# 1593K-WirelessTallyReceiver.net
KiCad netlist of a schematic drawn in EAGLE
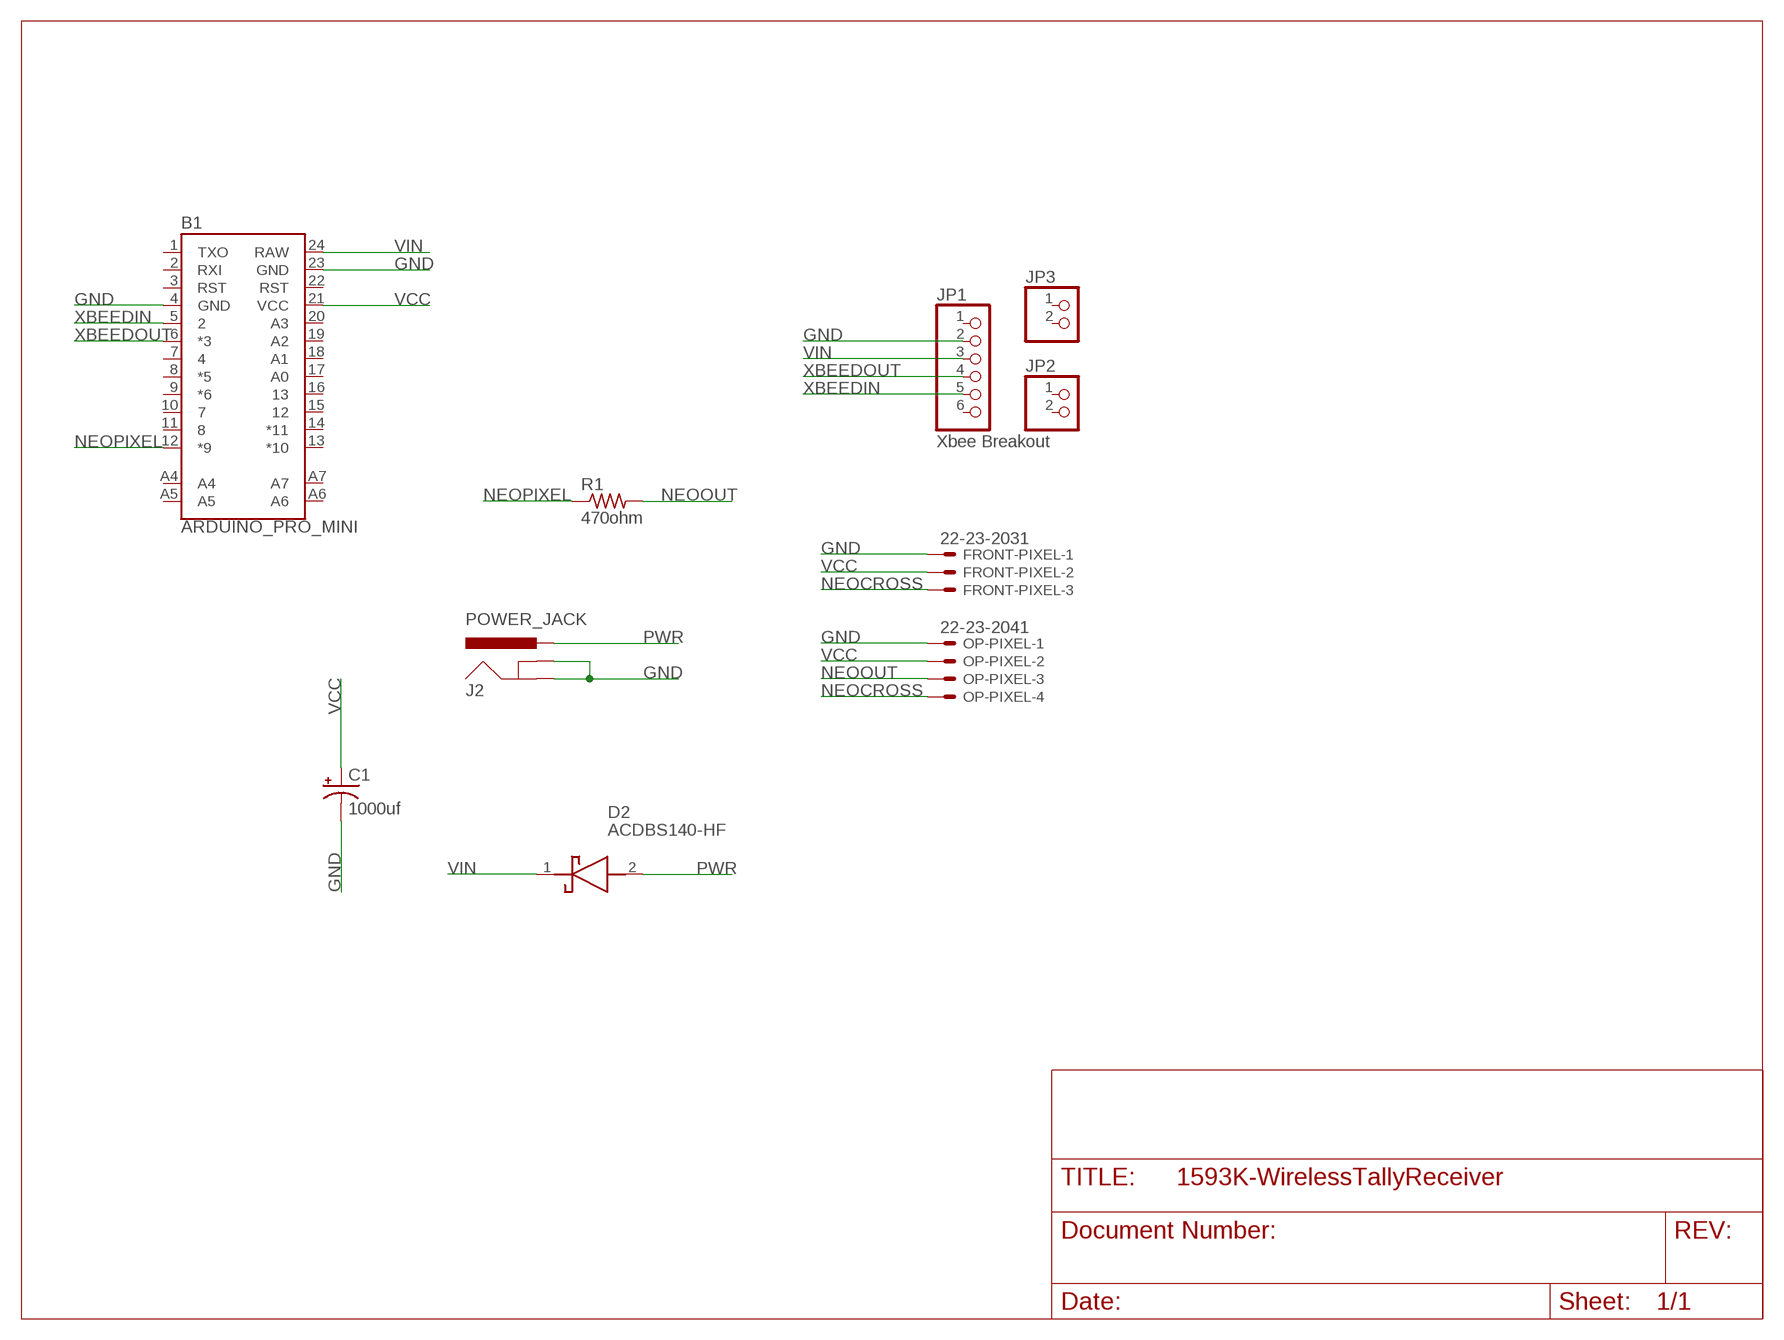
[diagram p0: schematic, sheet 1]

(export (version "E")
  (design (tool "Eeschema 10.0.6"))
  (components
    (comp (ref "B1")
      (value "ARDUINO_PRO_MINI")
      (footprint "eagle-import:ARDUINO_PRO_MINI")
      (libsource (lib "eagle-import") (part "ARDUINO_PRO_MINI"))
    )
    (comp (ref "C1")
      (value "1000uf")
      (footprint "eagle-import:CPOL-RADIAL-5MM-10MM")
      (libsource (lib "eagle-import") (part "1000UF-RADIAL-5MM-25V-20%"))
    )
    (comp (ref "D2")
      (value "ACDBS140-HF")
      (footprint "eagle-import:DIOM2013X100N")
      (fields (field (name "MOUSER_PART_NUMBER") "750-ACDBS140-HF"))
      (libsource (lib "eagle-import") (part "ACDBS140-HF"))
    )
    (comp (ref "FRONT-PIXEL")
      (value "22-23-2031")
      (footprint "eagle-import:22-23-2031")
      (fields (field (name "MF") "MOLEX"))
      (libsource (lib "eagle-import") (part "22-23-2031"))
    )
    (comp (ref "J2")
      (value "POWER_JACK")
      (footprint "eagle-import:POWER_JACK_PTH")
      (libsource (lib "eagle-import") (part "POWER_JACK"))
    )
    (comp (ref "JP1")
      (value "Xbee Breakout")
      (footprint "eagle-import:1X06")
      (libsource (lib "eagle-import") (part "PINHD-1X6"))
    )
    (comp (ref "JP2")
      (value "PINHD-1X2")
      (footprint "eagle-import:1X02")
      (libsource (lib "eagle-import") (part "PINHD-1X2"))
    )
    (comp (ref "JP3")
      (value "PINHD-1X2")
      (footprint "eagle-import:1X02")
      (libsource (lib "eagle-import") (part "PINHD-1X2"))
    )
    (comp (ref "OP-PIXEL")
      (value "22-23-2041")
      (footprint "eagle-import:22-23-2041")
      (fields (field (name "MF") "MOLEX"))
      (libsource (lib "eagle-import") (part "22-23-2041"))
    )
    (comp (ref "R1")
      (value "470ohm")
      (footprint "eagle-import:R0805")
      (libsource (lib "eagle-import") (part "R-US_R0805"))
    )
  )
  (nets
    (net (code "1") (name "/GND") (class "Default")
      (node (ref "B1") (pin "23") (pinfunction "GND_23") (pintype "power_in"))
      (node (ref "B1") (pin "4") (pinfunction "GND_4") (pintype "power_in"))
      (node (ref "C1") (pin "-") (pinfunction "-_-") (pintype "passive"))
      (node (ref "FRONT-PIXEL") (pin "1") (pinfunction "S_1") (pintype "passive"))
      (node (ref "J2") (pin "GND") (pinfunction "GND_GND") (pintype "bidirectional"))
      (node (ref "J2") (pin "GNDBREAK") (pinfunction "GNDBREAK_GNDBREAK") (pintype "bidirectional"))
      (node (ref "JP1") (pin "2") (pinfunction "2_2") (pintype "passive"))
      (node (ref "OP-PIXEL") (pin "1") (pinfunction "S_1") (pintype "passive"))
    )
    (net (code "2") (name "/NEOCROSS") (class "Default")
      (node (ref "FRONT-PIXEL") (pin "3") (pinfunction "S_3") (pintype "passive"))
      (node (ref "OP-PIXEL") (pin "4") (pinfunction "S_4") (pintype "passive"))
    )
    (net (code "3") (name "/NEOOUT") (class "Default")
      (node (ref "OP-PIXEL") (pin "3") (pinfunction "S_3") (pintype "passive"))
      (node (ref "R1") (pin "2") (pinfunction "2_2") (pintype "passive"))
    )
    (net (code "4") (name "/NEOPIXEL") (class "Default")
      (node (ref "B1") (pin "12") (pinfunction "*9_12") (pintype "bidirectional"))
      (node (ref "R1") (pin "1") (pinfunction "1_1") (pintype "passive"))
    )
    (net (code "5") (name "/PWR") (class "Default")
      (node (ref "D2") (pin "2") (pinfunction "A_2") (pintype "bidirectional"))
      (node (ref "J2") (pin "PWR") (pinfunction "PWR_PWR") (pintype "bidirectional"))
    )
    (net (code "6") (name "/VCC") (class "Default")
      (node (ref "B1") (pin "21") (pinfunction "VCC_21") (pintype "power_in"))
      (node (ref "C1") (pin "+") (pinfunction "+_+") (pintype "passive"))
      (node (ref "FRONT-PIXEL") (pin "2") (pinfunction "S_2") (pintype "passive"))
      (node (ref "OP-PIXEL") (pin "2") (pinfunction "S_2") (pintype "passive"))
    )
    (net (code "7") (name "/VIN") (class "Default")
      (node (ref "B1") (pin "24") (pinfunction "RAW_24") (pintype "power_in"))
      (node (ref "D2") (pin "1") (pinfunction "K_1") (pintype "bidirectional"))
      (node (ref "JP1") (pin "3") (pinfunction "3_3") (pintype "passive"))
    )
    (net (code "8") (name "/XBEEDIN") (class "Default")
      (node (ref "B1") (pin "5") (pinfunction "2_5") (pintype "bidirectional"))
      (node (ref "JP1") (pin "5") (pinfunction "5_5") (pintype "passive"))
    )
    (net (code "9") (name "/XBEEDOUT") (class "Default")
      (node (ref "B1") (pin "6") (pinfunction "*3_6") (pintype "bidirectional"))
      (node (ref "JP1") (pin "4") (pinfunction "4_4") (pintype "passive"))
    )
    (net (code "10") (name "unconnected-(B1-*5-Pad8)") (class "Default")
      (node (ref "B1") (pin "8") (pinfunction "*5_8") (pintype "bidirectional"))
    )
    (net (code "11") (name "unconnected-(B1-*6-Pad9)") (class "Default")
      (node (ref "B1") (pin "9") (pinfunction "*6_9") (pintype "bidirectional"))
    )
    (net (code "12") (name "unconnected-(B1-*10-Pad13)") (class "Default")
      (node (ref "B1") (pin "13") (pinfunction "*10_13") (pintype "bidirectional"))
    )
    (net (code "13") (name "unconnected-(B1-*11-Pad14)") (class "Default")
      (node (ref "B1") (pin "14") (pinfunction "*11_14") (pintype "bidirectional"))
    )
    (net (code "14") (name "unconnected-(B1-4-Pad7)") (class "Default")
      (node (ref "B1") (pin "7") (pinfunction "4_7") (pintype "bidirectional"))
    )
    (net (code "15") (name "unconnected-(B1-7-Pad10)") (class "Default")
      (node (ref "B1") (pin "10") (pinfunction "7_10") (pintype "bidirectional"))
    )
    (net (code "16") (name "unconnected-(B1-8-Pad11)") (class "Default")
      (node (ref "B1") (pin "11") (pinfunction "8_11") (pintype "bidirectional"))
    )
    (net (code "17") (name "unconnected-(B1-12-Pad15)") (class "Default")
      (node (ref "B1") (pin "15") (pinfunction "12_15") (pintype "bidirectional"))
    )
    (net (code "18") (name "unconnected-(B1-13-Pad16)") (class "Default")
      (node (ref "B1") (pin "16") (pinfunction "13_16") (pintype "bidirectional"))
    )
    (net (code "19") (name "unconnected-(B1-A0-Pad17)") (class "Default")
      (node (ref "B1") (pin "17") (pinfunction "A0_17") (pintype "bidirectional"))
    )
    (net (code "20") (name "unconnected-(B1-A1-Pad18)") (class "Default")
      (node (ref "B1") (pin "18") (pinfunction "A1_18") (pintype "bidirectional"))
    )
    (net (code "21") (name "unconnected-(B1-A2-Pad19)") (class "Default")
      (node (ref "B1") (pin "19") (pinfunction "A2_19") (pintype "bidirectional"))
    )
    (net (code "22") (name "unconnected-(B1-A3-Pad20)") (class "Default")
      (node (ref "B1") (pin "20") (pinfunction "A3_20") (pintype "bidirectional"))
    )
    (net (code "23") (name "unconnected-(B1-PadA4)") (class "Default")
      (node (ref "B1") (pin "A4") (pinfunction "A4_A4") (pintype "bidirectional"))
    )
    (net (code "24") (name "unconnected-(B1-PadA5)") (class "Default")
      (node (ref "B1") (pin "A5") (pinfunction "A5_A5") (pintype "bidirectional"))
    )
    (net (code "25") (name "unconnected-(B1-PadA6)") (class "Default")
      (node (ref "B1") (pin "A6") (pinfunction "A6_A6") (pintype "bidirectional"))
    )
    (net (code "26") (name "unconnected-(B1-PadA7)") (class "Default")
      (node (ref "B1") (pin "A7") (pinfunction "A7_A7") (pintype "bidirectional"))
    )
    (net (code "27") (name "unconnected-(B1-RST-Pad3)") (class "Default")
      (node (ref "B1") (pin "3") (pinfunction "RST_3") (pintype "bidirectional"))
    )
    (net (code "28") (name "unconnected-(B1-RST-Pad22)") (class "Default")
      (node (ref "B1") (pin "22") (pinfunction "RST_22") (pintype "bidirectional"))
    )
    (net (code "29") (name "unconnected-(B1-RXI-Pad2)") (class "Default")
      (node (ref "B1") (pin "2") (pinfunction "RXI_2") (pintype "bidirectional"))
    )
    (net (code "30") (name "unconnected-(B1-TXO-Pad1)") (class "Default")
      (node (ref "B1") (pin "1") (pinfunction "TXO_1") (pintype "bidirectional"))
    )
    (net (code "31") (name "unconnected-(JP1-Pad1)") (class "Default")
      (node (ref "JP1") (pin "1") (pinfunction "1_1") (pintype "passive"))
    )
    (net (code "32") (name "unconnected-(JP1-Pad6)") (class "Default")
      (node (ref "JP1") (pin "6") (pinfunction "6_6") (pintype "passive"))
    )
    (net (code "33") (name "unconnected-(JP2-Pad1)") (class "Default")
      (node (ref "JP2") (pin "1") (pinfunction "1_1") (pintype "passive"))
    )
    (net (code "34") (name "unconnected-(JP2-Pad2)") (class "Default")
      (node (ref "JP2") (pin "2") (pinfunction "2_2") (pintype "passive"))
    )
    (net (code "35") (name "unconnected-(JP3-Pad1)") (class "Default")
      (node (ref "JP3") (pin "1") (pinfunction "1_1") (pintype "passive"))
    )
    (net (code "36") (name "unconnected-(JP3-Pad2)") (class "Default")
      (node (ref "JP3") (pin "2") (pinfunction "2_2") (pintype "passive"))
    )
  )
)
